# DevBCU_v1_0.net
KiCad netlist of a schematic drawn in EAGLE
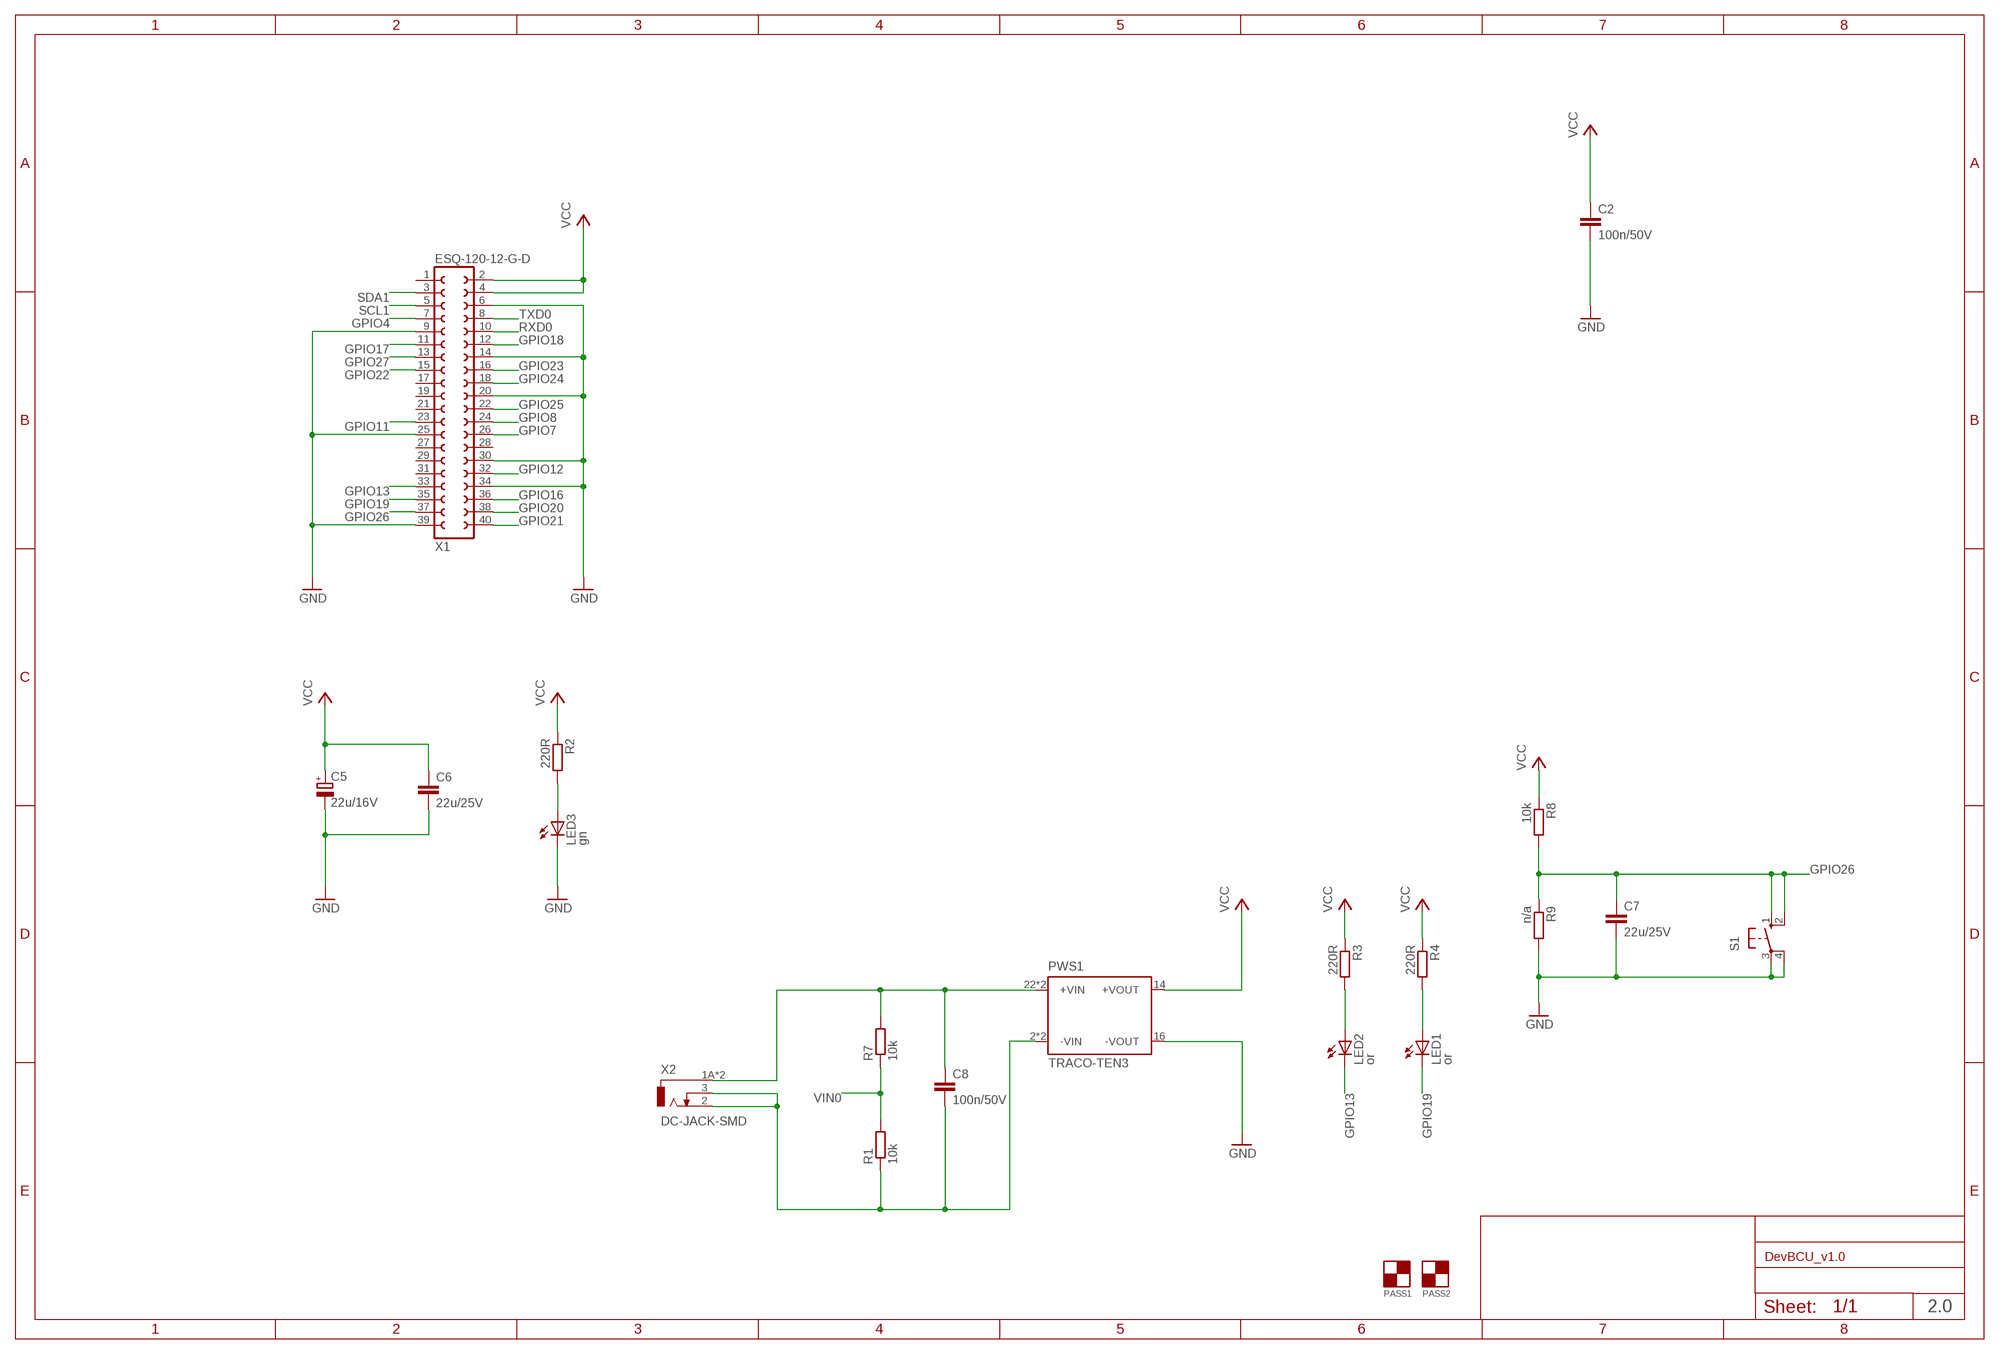
[diagram p0: schematic, sheet 1]

(export (version "E")
  (design (tool "Eeschema 10.0.6"))
  (components
    (comp (ref "C2")
      (value "100n/50V")
      (footprint "eagle-import:C0805")
      (libsource (lib "eagle-import") (part "C-EUC0805"))
    )
    (comp (ref "C5")
      (value "22u/16V")
      (footprint "eagle-import:B_3528-21R")
      (libsource (lib "eagle-import") (part "CPOL-EUB/3528-21R"))
    )
    (comp (ref "C6")
      (value "22u/25V")
      (footprint "eagle-import:C1210K")
      (libsource (lib "eagle-import") (part "C-EUC1210K"))
    )
    (comp (ref "C7")
      (value "22u/25V")
      (footprint "eagle-import:C1210K")
      (libsource (lib "eagle-import") (part "C-EUC1210K"))
    )
    (comp (ref "C8")
      (value "100n/50V")
      (footprint "eagle-import:C0805")
      (libsource (lib "eagle-import") (part "C-EUC0805"))
    )
    (comp (ref "LED1")
      (value "or")
      (footprint "eagle-import:CHIP-LED0603")
      (libsource (lib "eagle-import") (part "LEDCHIP-LED0603"))
    )
    (comp (ref "LED2")
      (value "or")
      (footprint "eagle-import:CHIP-LED0603")
      (libsource (lib "eagle-import") (part "LEDCHIP-LED0603"))
    )
    (comp (ref "LED3")
      (value "gn")
      (footprint "eagle-import:CHIP-LED0603")
      (libsource (lib "eagle-import") (part "LEDCHIP-LED0603"))
    )
    (comp (ref "PASS1")
      (value "MAKR1")
      (footprint "eagle-import:MARK1")
      (libsource (lib "eagle-import") (part "MAKR1"))
    )
    (comp (ref "PASS2")
      (value "MAKR1")
      (footprint "eagle-import:MARK1")
      (libsource (lib "eagle-import") (part "MAKR1"))
    )
    (comp (ref "PWS1")
      (value "TRACO-TEN3")
      (footprint "eagle-import:TRACO_TEN_3")
      (libsource (lib "eagle-import") (part "TRACO-TEN3"))
    )
    (comp (ref "R1")
      (value "10k")
      (footprint "eagle-import:M0805")
      (libsource (lib "eagle-import") (part "R-EU_M0805"))
    )
    (comp (ref "R2")
      (value "220R")
      (footprint "eagle-import:R0805")
      (libsource (lib "eagle-import") (part "R-EU_R0805"))
    )
    (comp (ref "R3")
      (value "220R")
      (footprint "eagle-import:R0805")
      (libsource (lib "eagle-import") (part "R-EU_R0805"))
    )
    (comp (ref "R4")
      (value "220R")
      (footprint "eagle-import:R0805")
      (libsource (lib "eagle-import") (part "R-EU_R0805"))
    )
    (comp (ref "R7")
      (value "10k")
      (footprint "eagle-import:M0805")
      (libsource (lib "eagle-import") (part "R-EU_M0805"))
    )
    (comp (ref "R8")
      (value "10k")
      (footprint "eagle-import:R0805")
      (libsource (lib "eagle-import") (part "R-EU_R0805"))
    )
    (comp (ref "R9")
      (value "n/a")
      (footprint "eagle-import:R0805")
      (libsource (lib "eagle-import") (part "R-EU_R0805"))
    )
    (comp (ref "S1")
      (value "10-XXS")
      (footprint "eagle-import:B3FS-10XX")
      (libsource (lib "eagle-import") (part "10-XXS"))
    )
    (comp (ref "X1")
      (value "ESQ-120-12-G-D")
      (footprint "eagle-import:FE20-2")
      (libsource (lib "eagle-import") (part "FE20-2"))
    )
    (comp (ref "X2")
      (value "DC-JACK-SMD")
      (footprint "eagle-import:694_1XX_106_102")
      (libsource (lib "eagle-import") (part "DC-JACK-SMD"))
    )
  )
  (nets
    (net (code "1") (name "/GPIO4") (class "Default")
      (node (ref "X1") (pin "7") (pinfunction "7_7") (pintype "passive"))
    )
    (net (code "2") (name "/GPIO7") (class "Default")
      (node (ref "X1") (pin "26") (pinfunction "26_26") (pintype "passive"))
    )
    (net (code "3") (name "/GPIO8") (class "Default")
      (node (ref "X1") (pin "24") (pinfunction "24_24") (pintype "passive"))
    )
    (net (code "4") (name "/GPIO11") (class "Default")
      (node (ref "X1") (pin "23") (pinfunction "23_23") (pintype "passive"))
    )
    (net (code "5") (name "/GPIO12") (class "Default")
      (node (ref "X1") (pin "32") (pinfunction "32_32") (pintype "passive"))
    )
    (net (code "6") (name "/GPIO13") (class "Default")
      (node (ref "LED2") (pin "C") (pinfunction "C_C") (pintype "passive"))
      (node (ref "X1") (pin "33") (pinfunction "33_33") (pintype "passive"))
    )
    (net (code "7") (name "/GPIO16") (class "Default")
      (node (ref "X1") (pin "36") (pinfunction "36_36") (pintype "passive"))
    )
    (net (code "8") (name "/GPIO17") (class "Default")
      (node (ref "X1") (pin "11") (pinfunction "11_11") (pintype "passive"))
    )
    (net (code "9") (name "/GPIO18") (class "Default")
      (node (ref "X1") (pin "12") (pinfunction "12_12") (pintype "passive"))
    )
    (net (code "10") (name "/GPIO19") (class "Default")
      (node (ref "LED1") (pin "C") (pinfunction "C_C") (pintype "passive"))
      (node (ref "X1") (pin "35") (pinfunction "35_35") (pintype "passive"))
    )
    (net (code "11") (name "/GPIO20") (class "Default")
      (node (ref "X1") (pin "38") (pinfunction "38_38") (pintype "passive"))
    )
    (net (code "12") (name "/GPIO21") (class "Default")
      (node (ref "X1") (pin "40") (pinfunction "40_40") (pintype "passive"))
    )
    (net (code "13") (name "/GPIO22") (class "Default")
      (node (ref "X1") (pin "15") (pinfunction "15_15") (pintype "passive"))
    )
    (net (code "14") (name "/GPIO23") (class "Default")
      (node (ref "X1") (pin "16") (pinfunction "16_16") (pintype "passive"))
    )
    (net (code "15") (name "/GPIO24") (class "Default")
      (node (ref "X1") (pin "18") (pinfunction "18_18") (pintype "passive"))
    )
    (net (code "16") (name "/GPIO25") (class "Default")
      (node (ref "X1") (pin "22") (pinfunction "22_22") (pintype "passive"))
    )
    (net (code "17") (name "/GPIO26") (class "Default")
      (node (ref "C7") (pin "1") (pinfunction "1_1") (pintype "passive"))
      (node (ref "R8") (pin "2") (pinfunction "2_2") (pintype "passive"))
      (node (ref "R9") (pin "1") (pinfunction "1_1") (pintype "passive"))
      (node (ref "S1") (pin "1") (pinfunction "S_1") (pintype "passive"))
      (node (ref "S1") (pin "2") (pinfunction "S1_2") (pintype "passive"))
      (node (ref "X1") (pin "37") (pinfunction "37_37") (pintype "passive"))
    )
    (net (code "18") (name "/GPIO27") (class "Default")
      (node (ref "X1") (pin "13") (pinfunction "13_13") (pintype "passive"))
    )
    (net (code "19") (name "/RXD0") (class "Default")
      (node (ref "X1") (pin "10") (pinfunction "10_10") (pintype "passive"))
    )
    (net (code "20") (name "/SCL1") (class "Default")
      (node (ref "X1") (pin "5") (pinfunction "5_5") (pintype "passive"))
    )
    (net (code "21") (name "/SDA1") (class "Default")
      (node (ref "X1") (pin "3") (pinfunction "3_3") (pintype "passive"))
    )
    (net (code "22") (name "/TXD0") (class "Default")
      (node (ref "X1") (pin "8") (pinfunction "8_8") (pintype "passive"))
    )
    (net (code "23") (name "/VIN0") (class "Default")
      (node (ref "R1") (pin "2") (pinfunction "2_2") (pintype "passive"))
      (node (ref "R7") (pin "1") (pinfunction "1_1") (pintype "passive"))
    )
    (net (code "24") (name "GND") (class "Default")
      (node (ref "C2") (pin "2") (pinfunction "2_2") (pintype "passive"))
      (node (ref "C5") (pin "-") (pinfunction "-_-") (pintype "passive"))
      (node (ref "C6") (pin "2") (pinfunction "2_2") (pintype "passive"))
      (node (ref "C7") (pin "2") (pinfunction "2_2") (pintype "passive"))
      (node (ref "LED3") (pin "C") (pinfunction "C_C") (pintype "passive"))
      (node (ref "PWS1") (pin "16") (pinfunction "-VOUT_16") (pintype "passive"))
      (node (ref "R9") (pin "2") (pinfunction "2_2") (pintype "passive"))
      (node (ref "S1") (pin "3") (pinfunction "P_3") (pintype "passive"))
      (node (ref "S1") (pin "4") (pinfunction "P1_4") (pintype "passive"))
      (node (ref "X1") (pin "14") (pinfunction "14_14") (pintype "passive"))
      (node (ref "X1") (pin "20") (pinfunction "20_20") (pintype "passive"))
      (node (ref "X1") (pin "25") (pinfunction "25_25") (pintype "passive"))
      (node (ref "X1") (pin "30") (pinfunction "30_30") (pintype "passive"))
      (node (ref "X1") (pin "34") (pinfunction "34_34") (pintype "passive"))
      (node (ref "X1") (pin "39") (pinfunction "39_39") (pintype "passive"))
      (node (ref "X1") (pin "6") (pinfunction "6_6") (pintype "passive"))
      (node (ref "X1") (pin "9") (pinfunction "9_9") (pintype "passive"))
    )
    (net (code "25") (name "Net-(C8-Pad1)") (class "Default")
      (node (ref "C8") (pin "1") (pinfunction "1_1") (pintype "passive"))
      (node (ref "PWS1") (pin "22") (pinfunction "+VIN_22") (pintype "input"))
      (node (ref "PWS1") (pin "23") (pinfunction "+VIN_23") (pintype "input"))
      (node (ref "R7") (pin "2") (pinfunction "2_2") (pintype "passive"))
      (node (ref "X2") (pin "1A") (pinfunction "1_1A") (pintype "passive"))
      (node (ref "X2") (pin "1B") (pinfunction "1_1B") (pintype "passive"))
    )
    (net (code "26") (name "Net-(C8-Pad2)") (class "Default")
      (node (ref "C8") (pin "2") (pinfunction "2_2") (pintype "passive"))
      (node (ref "PWS1") (pin "2") (pinfunction "-VIN_2") (pintype "input"))
      (node (ref "PWS1") (pin "3") (pinfunction "-VIN_3") (pintype "input"))
      (node (ref "R1") (pin "1") (pinfunction "1_1") (pintype "passive"))
      (node (ref "X2") (pin "2") (pinfunction "2_2") (pintype "passive"))
      (node (ref "X2") (pin "3") (pinfunction "3_3") (pintype "passive"))
    )
    (net (code "27") (name "Net-(LED1-PadA)") (class "Default")
      (node (ref "LED1") (pin "A") (pinfunction "A_A") (pintype "passive"))
      (node (ref "R4") (pin "2") (pinfunction "2_2") (pintype "passive"))
    )
    (net (code "28") (name "Net-(LED2-PadA)") (class "Default")
      (node (ref "LED2") (pin "A") (pinfunction "A_A") (pintype "passive"))
      (node (ref "R3") (pin "2") (pinfunction "2_2") (pintype "passive"))
    )
    (net (code "29") (name "Net-(LED3-PadA)") (class "Default")
      (node (ref "LED3") (pin "A") (pinfunction "A_A") (pintype "passive"))
      (node (ref "R2") (pin "2") (pinfunction "2_2") (pintype "passive"))
    )
    (net (code "30") (name "VCC") (class "Default")
      (node (ref "C2") (pin "1") (pinfunction "1_1") (pintype "passive"))
      (node (ref "C5") (pin "+") (pinfunction "+_+") (pintype "passive"))
      (node (ref "C6") (pin "1") (pinfunction "1_1") (pintype "passive"))
      (node (ref "PWS1") (pin "14") (pinfunction "+VOUT_14") (pintype "passive"))
      (node (ref "R2") (pin "1") (pinfunction "1_1") (pintype "passive"))
      (node (ref "R3") (pin "1") (pinfunction "1_1") (pintype "passive"))
      (node (ref "R4") (pin "1") (pinfunction "1_1") (pintype "passive"))
      (node (ref "R8") (pin "1") (pinfunction "1_1") (pintype "passive"))
      (node (ref "X1") (pin "2") (pinfunction "2_2") (pintype "passive"))
      (node (ref "X1") (pin "4") (pinfunction "4_4") (pintype "passive"))
    )
    (net (code "31") (name "unconnected-(X1-Pad1)") (class "Default")
      (node (ref "X1") (pin "1") (pinfunction "1_1") (pintype "passive"))
    )
    (net (code "32") (name "unconnected-(X1-Pad17)") (class "Default")
      (node (ref "X1") (pin "17") (pinfunction "17_17") (pintype "passive"))
    )
    (net (code "33") (name "unconnected-(X1-Pad19)") (class "Default")
      (node (ref "X1") (pin "19") (pinfunction "19_19") (pintype "passive"))
    )
    (net (code "34") (name "unconnected-(X1-Pad21)") (class "Default")
      (node (ref "X1") (pin "21") (pinfunction "21_21") (pintype "passive"))
    )
    (net (code "35") (name "unconnected-(X1-Pad27)") (class "Default")
      (node (ref "X1") (pin "27") (pinfunction "27_27") (pintype "passive"))
    )
    (net (code "36") (name "unconnected-(X1-Pad28)") (class "Default")
      (node (ref "X1") (pin "28") (pinfunction "28_28") (pintype "passive"))
    )
    (net (code "37") (name "unconnected-(X1-Pad29)") (class "Default")
      (node (ref "X1") (pin "29") (pinfunction "29_29") (pintype "passive"))
    )
    (net (code "38") (name "unconnected-(X1-Pad31)") (class "Default")
      (node (ref "X1") (pin "31") (pinfunction "31_31") (pintype "passive"))
    )
  )
)
